# Boost_Conv_V1_0_Control_Sch.net
KiCad netlist of a schematic drawn in Altium Designer
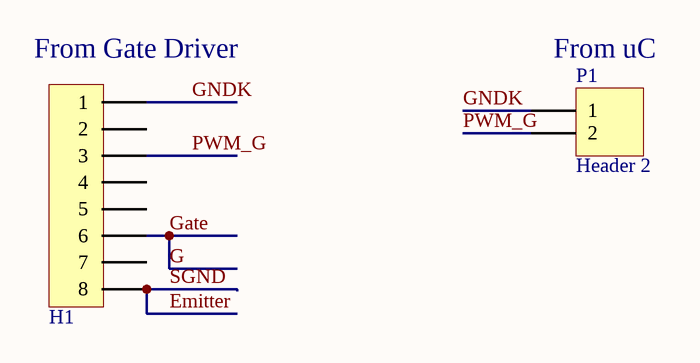
[diagram p0: Boost_Conv_V1.0_Control_Sch.SchDoc]

(export (version "E")
  (design (tool "Eeschema 10.0.6"))
  (components
    (comp (ref "H1")
      (value "H2*8")
      (footprint "HDR2X8")
      (libsource (lib "Schlib1-GATE-DRV-SMPS-1") (part "Header 8X2"))
    )
    (comp (ref "P1")
      (value "Header 2")
      (footprint "HDR1X2")
      (description "Header, 2-Pin")
      (fields (field (name "PUBLISHER") "Altium Limited"))
      (libsource (lib "Miscellaneous Connectors") (part "Header 2"))
    )
  )
  (nets
    (net (code "1") (name "/Emitter") (class "Default")
      (node (ref "H1") (pin "8") (pinfunction "8_8") (pintype "passive"))
    )
    (net (code "2") (name "/G") (class "Default")
      (node (ref "H1") (pin "6") (pinfunction "6_6") (pintype "passive"))
    )
    (net (code "3") (name "/GNDK") (class "Default")
      (node (ref "H1") (pin "1") (pinfunction "1_1") (pintype "passive"))
      (node (ref "P1") (pin "1") (pinfunction "1_1") (pintype "passive"))
    )
    (net (code "4") (name "/PWM_G") (class "Default")
      (node (ref "H1") (pin "3") (pinfunction "3_3") (pintype "passive"))
      (node (ref "P1") (pin "2") (pinfunction "2_2") (pintype "passive"))
    )
    (net (code "5") (name "unconnected-(H1-Pad2)") (class "Default")
      (node (ref "H1") (pin "2") (pinfunction "2_2") (pintype "passive"))
    )
    (net (code "6") (name "unconnected-(H1-Pad4)") (class "Default")
      (node (ref "H1") (pin "4") (pinfunction "4_4") (pintype "passive"))
    )
    (net (code "7") (name "unconnected-(H1-Pad5)") (class "Default")
      (node (ref "H1") (pin "5") (pinfunction "5_5") (pintype "passive"))
    )
    (net (code "8") (name "unconnected-(H1-Pad7)") (class "Default")
      (node (ref "H1") (pin "7") (pinfunction "7_7") (pintype "passive"))
    )
  )
)
